# avoccado-panel-multi-1.net
KiCad netlist of a schematic drawn in EAGLE
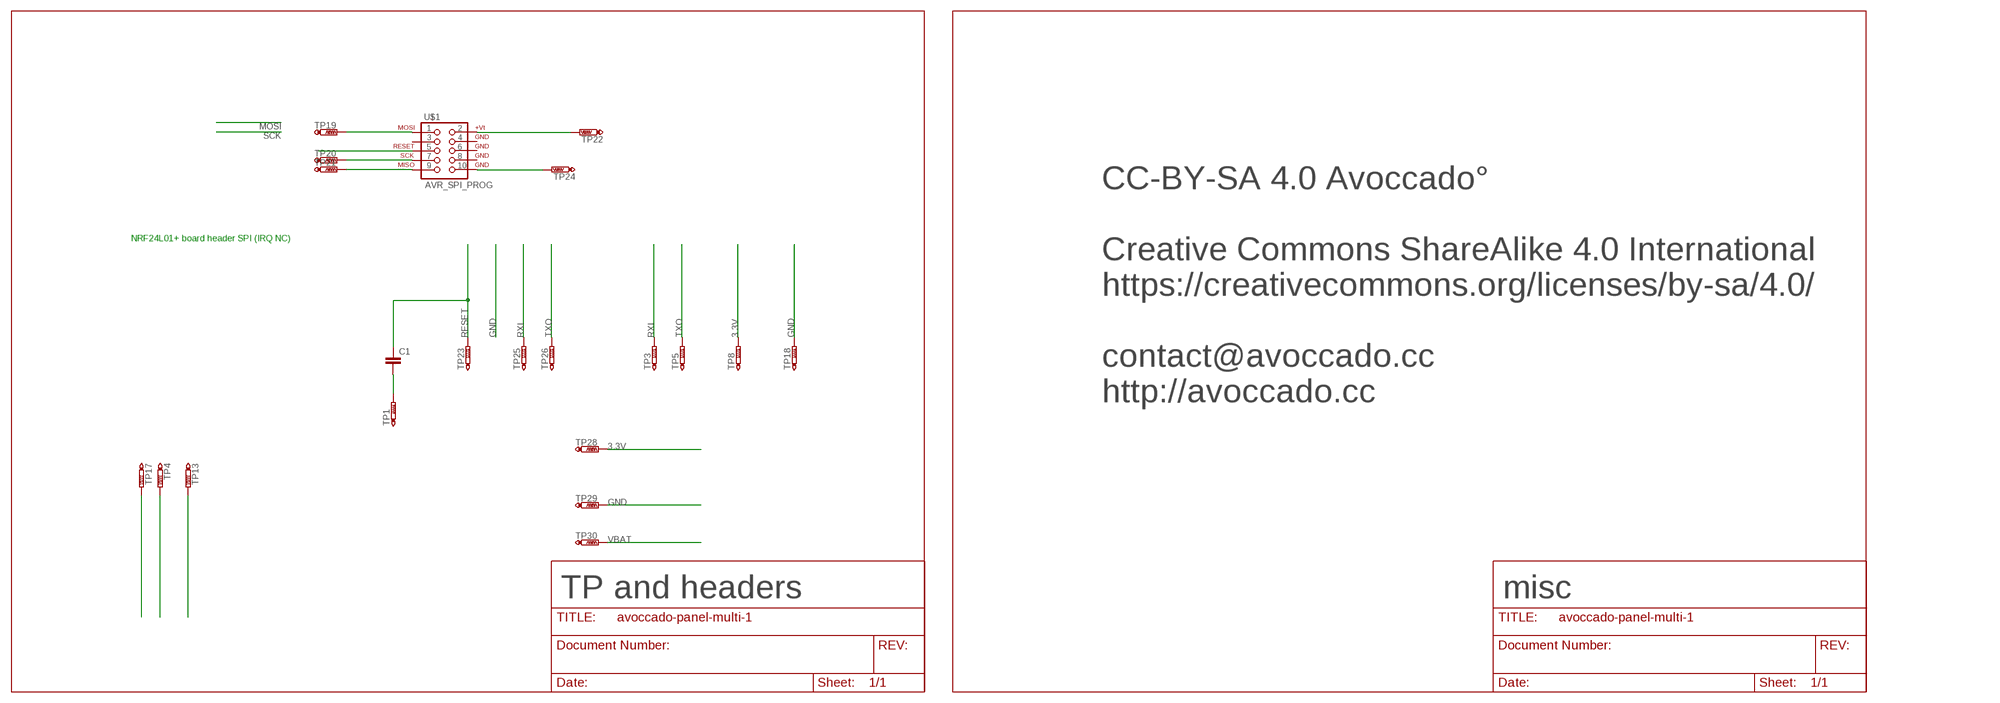
[diagram p0: schematic, sheet 1]

(export (version "E")
  (design (tool "Eeschema 10.0.6"))
  (components
    (comp (ref "C1")
      (value "C-EUC0402")
      (footprint "eagle-import:C0402")
      (libsource (lib "eagle-import") (part "C-EUC0402"))
    )
    (comp (ref "TP1")
      (value "PTR1PAD1-13")
      (footprint "eagle-import:P1-13")
      (libsource (lib "eagle-import") (part "PTR1PAD1-13"))
    )
    (comp (ref "TP3")
      (value "PTR1PAD1-13")
      (footprint "eagle-import:P1-13")
      (libsource (lib "eagle-import") (part "PTR1PAD1-13"))
    )
    (comp (ref "TP4")
      (value "PTR1PAD1-13")
      (footprint "eagle-import:P1-13")
      (libsource (lib "eagle-import") (part "PTR1PAD1-13"))
    )
    (comp (ref "TP5")
      (value "PTR1PAD1-13")
      (footprint "eagle-import:P1-13")
      (libsource (lib "eagle-import") (part "PTR1PAD1-13"))
    )
    (comp (ref "TP8")
      (value "PTR1PAD1-13")
      (footprint "eagle-import:P1-13")
      (libsource (lib "eagle-import") (part "PTR1PAD1-13"))
    )
    (comp (ref "TP13")
      (value "PTR1PAD1-13")
      (footprint "eagle-import:P1-13")
      (libsource (lib "eagle-import") (part "PTR1PAD1-13"))
    )
    (comp (ref "TP17")
      (value "PTR1PAD1-13")
      (footprint "eagle-import:P1-13")
      (libsource (lib "eagle-import") (part "PTR1PAD1-13"))
    )
    (comp (ref "TP18")
      (value "PTR1PAD1-13")
      (footprint "eagle-import:P1-13")
      (libsource (lib "eagle-import") (part "PTR1PAD1-13"))
    )
    (comp (ref "TP19")
      (value "PTR1PAD1-13")
      (footprint "eagle-import:P1-13")
      (libsource (lib "eagle-import") (part "PTR1PAD1-13"))
    )
    (comp (ref "TP20")
      (value "PTR1PAD1-13")
      (footprint "eagle-import:P1-13")
      (libsource (lib "eagle-import") (part "PTR1PAD1-13"))
    )
    (comp (ref "TP21")
      (value "PTR1PAD1-13")
      (footprint "eagle-import:P1-13")
      (libsource (lib "eagle-import") (part "PTR1PAD1-13"))
    )
    (comp (ref "TP22")
      (value "PTR1PAD1-13")
      (footprint "eagle-import:P1-13")
      (libsource (lib "eagle-import") (part "PTR1PAD1-13"))
    )
    (comp (ref "TP23")
      (value "PTR1PAD1-13")
      (footprint "eagle-import:P1-13")
      (libsource (lib "eagle-import") (part "PTR1PAD1-13"))
    )
    (comp (ref "TP24")
      (value "PTR1PAD1-13")
      (footprint "eagle-import:P1-13")
      (libsource (lib "eagle-import") (part "PTR1PAD1-13"))
    )
    (comp (ref "TP25")
      (value "PTR1PAD1-13")
      (footprint "eagle-import:P1-13")
      (libsource (lib "eagle-import") (part "PTR1PAD1-13"))
    )
    (comp (ref "TP26")
      (value "PTR1PAD1-13")
      (footprint "eagle-import:P1-13")
      (libsource (lib "eagle-import") (part "PTR1PAD1-13"))
    )
    (comp (ref "TP28")
      (value "PTR1PAD1-13")
      (footprint "eagle-import:P1-13")
      (libsource (lib "eagle-import") (part "PTR1PAD1-13"))
    )
    (comp (ref "TP29")
      (value "PTR1PAD1-13")
      (footprint "eagle-import:P1-13")
      (libsource (lib "eagle-import") (part "PTR1PAD1-13"))
    )
    (comp (ref "TP30")
      (value "PTR1PAD1-13")
      (footprint "eagle-import:P1-13")
      (libsource (lib "eagle-import") (part "PTR1PAD1-13"))
    )
    (comp (ref "U$1")
      (value "AVR_SPI_PROG")
      (footprint "eagle-import:AVR_ICSP")
      (libsource (lib "eagle-import") (part "AVR_SPI_PROG"))
    )
  )
  (nets
    (net (code "1") (name "/3.3V") (class "Default")
      (node (ref "TP22") (pin "TP") (pinfunction "TP_TP") (pintype "input"))
      (node (ref "TP28") (pin "TP") (pinfunction "TP_TP") (pintype "input"))
      (node (ref "TP8") (pin "TP") (pinfunction "TP_TP") (pintype "input"))
      (node (ref "U$1") (pin "2") (pinfunction "2_2") (pintype "passive"))
    )
    (net (code "2") (name "/GND") (class "Default")
      (node (ref "TP18") (pin "TP") (pinfunction "TP_TP") (pintype "input"))
      (node (ref "TP24") (pin "TP") (pinfunction "TP_TP") (pintype "input"))
      (node (ref "TP29") (pin "TP") (pinfunction "TP_TP") (pintype "input"))
      (node (ref "U$1") (pin "10") (pinfunction "10_10") (pintype "passive"))
    )
    (net (code "3") (name "/MOSI") (class "Default")
      (node (ref "TP19") (pin "TP") (pinfunction "TP_TP") (pintype "input"))
      (node (ref "U$1") (pin "1") (pinfunction "1_1") (pintype "passive"))
    )
    (net (code "4") (name "/RESET") (class "Default")
      (node (ref "C1") (pin "1") (pinfunction "1_1") (pintype "passive"))
      (node (ref "TP23") (pin "TP") (pinfunction "TP_TP") (pintype "input"))
      (node (ref "U$1") (pin "5") (pinfunction "5_5") (pintype "passive"))
    )
    (net (code "5") (name "/RXI") (class "Default")
      (node (ref "TP25") (pin "TP") (pinfunction "TP_TP") (pintype "input"))
      (node (ref "TP3") (pin "TP") (pinfunction "TP_TP") (pintype "input"))
    )
    (net (code "6") (name "/SCK") (class "Default")
      (node (ref "TP20") (pin "TP") (pinfunction "TP_TP") (pintype "input"))
      (node (ref "U$1") (pin "7") (pinfunction "7_7") (pintype "passive"))
    )
    (net (code "7") (name "/TXO") (class "Default")
      (node (ref "TP26") (pin "TP") (pinfunction "TP_TP") (pintype "input"))
      (node (ref "TP5") (pin "TP") (pinfunction "TP_TP") (pintype "input"))
    )
    (net (code "8") (name "/VBAT") (class "Default")
      (node (ref "TP30") (pin "TP") (pinfunction "TP_TP") (pintype "input"))
    )
    (net (code "9") (name "Net-(C1-Pad2)") (class "Default")
      (node (ref "C1") (pin "2") (pinfunction "2_2") (pintype "passive"))
      (node (ref "TP1") (pin "TP") (pinfunction "TP_TP") (pintype "input"))
    )
    (net (code "10") (name "Net-(TP21-PadTP)") (class "Default")
      (node (ref "TP21") (pin "TP") (pinfunction "TP_TP") (pintype "input"))
      (node (ref "U$1") (pin "9") (pinfunction "9_9") (pintype "passive"))
    )
    (net (code "11") (name "unconnected-(TP4-PadTP)") (class "Default")
      (node (ref "TP4") (pin "TP") (pinfunction "TP_TP") (pintype "input"))
    )
    (net (code "12") (name "unconnected-(TP13-PadTP)") (class "Default")
      (node (ref "TP13") (pin "TP") (pinfunction "TP_TP") (pintype "input"))
    )
    (net (code "13") (name "unconnected-(TP17-PadTP)") (class "Default")
      (node (ref "TP17") (pin "TP") (pinfunction "TP_TP") (pintype "input"))
    )
    (net (code "14") (name "unconnected-(U$1-Pad3)") (class "Default")
      (node (ref "U$1") (pin "3") (pinfunction "3_3") (pintype "passive"))
    )
    (net (code "15") (name "unconnected-(U$1-Pad4)") (class "Default")
      (node (ref "U$1") (pin "4") (pinfunction "4_4") (pintype "passive"))
    )
    (net (code "16") (name "unconnected-(U$1-Pad6)") (class "Default")
      (node (ref "U$1") (pin "6") (pinfunction "6_6") (pintype "passive"))
    )
    (net (code "17") (name "unconnected-(U$1-Pad8)") (class "Default")
      (node (ref "U$1") (pin "8") (pinfunction "8_8") (pintype "passive"))
    )
  )
)
